# Main.net
KiCad netlist of a schematic drawn in Altium Designer
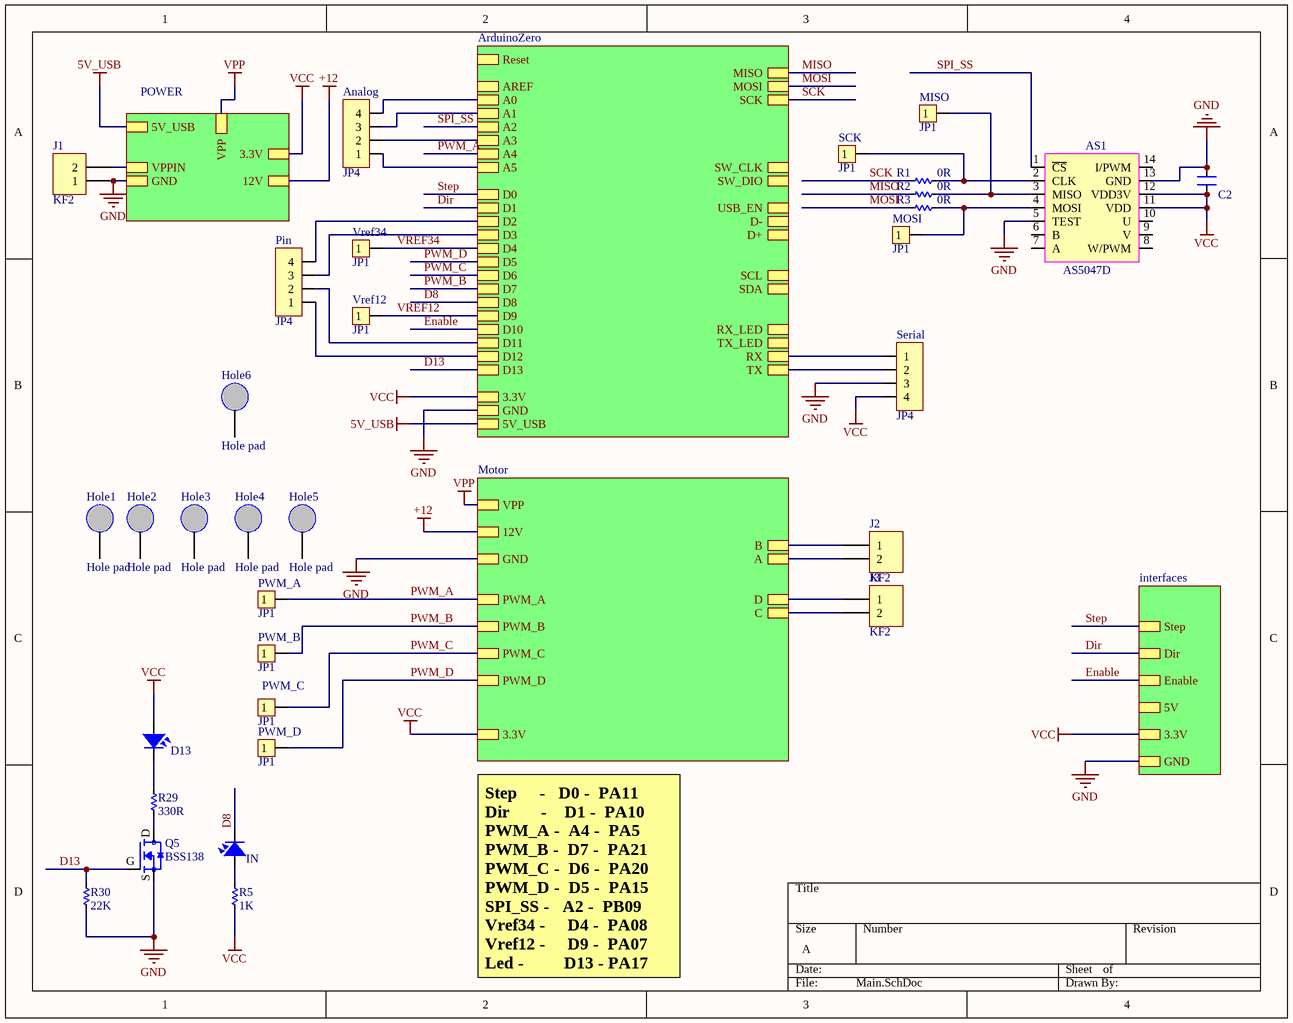
[diagram p0: Main.SchDoc]

(export (version "E")
  (design (tool "Eeschema 10.0.6"))
  (components
    (comp (ref "Analog")
      (value "JP4")
      (footprint "JP4-C1T")
      (description "WR-PHD 2.54 mm Angled Socket Header")
      (fields
        (field (name "MANUFACTURER") "Würth Elektronik eiSos GmbH")
        (field (name "PARTNO") "613004143121")
        (field (name "CREATED BY") "Karrer Zheng")
      )
      (libsource (lib "") (part "JP4_1"))
    )
    (comp (ref "AS1")
      (value "AS5047D")
      (footprint "AS5047D_Module")
      (fields (field (name "VOLTAGE") "0"))
      (libsource (lib "nhan") (part "AS5047D"))
    )
    (comp (ref "C2") (value "CN") (footprint "CN-SMD-0603_big") (libsource (lib "nhan") (part "CN")))
    (comp (ref "D13") (value "LED") (footprint "LED-0805-Blue") (libsource (lib "LIBRARY") (part "LED SMD")))
    (comp (ref "Hole1") (value "Hole pad") (footprint "HolePad") (libsource (lib "nhan") (part "Hole pad")))
    (comp (ref "Hole2") (value "Hole pad") (footprint "HolePad") (libsource (lib "nhan") (part "Hole pad")))
    (comp (ref "Hole3") (value "Hole pad") (footprint "HolePad") (libsource (lib "nhan") (part "Hole pad")))
    (comp (ref "Hole4") (value "Hole pad") (footprint "HolePad") (libsource (lib "nhan") (part "Hole pad")))
    (comp (ref "Hole5") (value "Hole pad") (footprint "HolePad") (libsource (lib "nhan") (part "Hole pad")))
    (comp (ref "Hole6") (value "Hole pad") (footprint "HolePad") (libsource (lib "nhan") (part "Hole pad")))
    (comp (ref "IN") (value "LED") (footprint "LED-0805-Blue") (libsource (lib "LIBRARY") (part "LED SMD")))
    (comp (ref "J1")
      (value "KF2")
      (footprint "KF2-5.08T")
      (fields
        (field (name "MANUFACTURER") "Würth Elektronik eiSos GmbH")
        (field (name "PARTNO") "691103110002")
        (field (name "CREATED BY") "Karrer Zheng")
      )
      (libsource (lib "") (part "KF2_1"))
    )
    (comp (ref "J2")
      (value "KF2")
      (footprint "KF2-5.08T")
      (fields
        (field (name "MANUFACTURER") "Würth Elektronik eiSos GmbH")
        (field (name "PARTNO") "691103110002")
        (field (name "CREATED BY") "Karrer Zheng")
      )
      (libsource (lib "BanLinhKien") (part "KF2"))
    )
    (comp (ref "J3")
      (value "KF2")
      (footprint "KF2-5.08T")
      (fields
        (field (name "MANUFACTURER") "Würth Elektronik eiSos GmbH")
        (field (name "PARTNO") "691103110002")
        (field (name "CREATED BY") "Karrer Zheng")
      )
      (libsource (lib "BanLinhKien") (part "KF2"))
    )
    (comp (ref "MISO")
      (value "JP1")
      (footprint "JP1-D1T")
      (description "WR-PHD 2.54 mm Angled Socket Header")
      (fields
        (field (name "MANUFACTURER") "Würth Elektronik eiSos GmbH")
        (field (name "PARTNO") "613002143121")
        (field (name "CREATED BY") "Karrer Zheng")
      )
      (libsource (lib "LIBRARY") (part "JP1"))
    )
    (comp (ref "MOSI")
      (value "JP1")
      (footprint "JP1-D1T")
      (description "WR-PHD 2.54 mm Angled Socket Header")
      (fields
        (field (name "MANUFACTURER") "Würth Elektronik eiSos GmbH")
        (field (name "PARTNO") "613002143121")
        (field (name "CREATED BY") "Karrer Zheng")
      )
      (libsource (lib "LIBRARY") (part "JP1"))
    )
    (comp (ref "Pin")
      (value "JP4")
      (footprint "JP4-C1T")
      (description "WR-PHD 2.54 mm Angled Socket Header")
      (fields
        (field (name "MANUFACTURER") "Würth Elektronik eiSos GmbH")
        (field (name "PARTNO") "613004143121")
        (field (name "CREATED BY") "Karrer Zheng")
      )
      (libsource (lib "") (part "JP4_1"))
    )
    (comp (ref "PWM_A")
      (value "JP1")
      (footprint "JP1-D1T")
      (description "WR-PHD 2.54 mm Angled Socket Header")
      (fields
        (field (name "MANUFACTURER") "Würth Elektronik eiSos GmbH")
        (field (name "PARTNO") "613002143121")
        (field (name "CREATED BY") "Karrer Zheng")
      )
      (libsource (lib "LIBRARY") (part "JP1"))
    )
    (comp (ref "PWM_B")
      (value "JP1")
      (footprint "JP1-D1T")
      (description "WR-PHD 2.54 mm Angled Socket Header")
      (fields
        (field (name "MANUFACTURER") "Würth Elektronik eiSos GmbH")
        (field (name "PARTNO") "613002143121")
        (field (name "CREATED BY") "Karrer Zheng")
      )
      (libsource (lib "LIBRARY") (part "JP1"))
    )
    (comp (ref "PWM_C")
      (value "JP1")
      (footprint "JP1-D1T")
      (description "WR-PHD 2.54 mm Angled Socket Header")
      (fields
        (field (name "MANUFACTURER") "Würth Elektronik eiSos GmbH")
        (field (name "PARTNO") "613002143121")
        (field (name "CREATED BY") "Karrer Zheng")
      )
      (libsource (lib "LIBRARY") (part "JP1"))
    )
    (comp (ref "PWM_D")
      (value "JP1")
      (footprint "JP1-D1T")
      (description "WR-PHD 2.54 mm Angled Socket Header")
      (fields
        (field (name "MANUFACTURER") "Würth Elektronik eiSos GmbH")
        (field (name "PARTNO") "613002143121")
        (field (name "CREATED BY") "Karrer Zheng")
      )
      (libsource (lib "LIBRARY") (part "JP1"))
    )
    (comp (ref "Q5")
      (value "BSS138")
      (footprint "SOT23-bss138")
      (description "N-Channel 50V 220mA _Ta_ 360mW _Ta_ Surface Mount Die")
      (fields (field (name "MF") "MICROSS/On Semiconductor"))
      (libsource (lib "nhan") (part "BSS138"))
    )
    (comp (ref "R1") (value "0R") (footprint "RES-SMD-0603_BIG") (libsource (lib "nhan") (part "R")))
    (comp (ref "R2") (value "0R") (footprint "RES-SMD-0603_BIG") (libsource (lib "nhan") (part "R")))
    (comp (ref "R3") (value "0R") (footprint "RES-SMD-0603_BIG") (libsource (lib "nhan") (part "R")))
    (comp (ref "R5") (value "1K") (footprint "RES-SMD-0603_BIG") (libsource (lib "nhan") (part "R")))
    (comp (ref "R29") (value "330R") (footprint "RES-SMD-0603_BIG") (libsource (lib "nhan") (part "R")))
    (comp (ref "R30") (value "22K") (footprint "RES-SMD-0603_BIG") (libsource (lib "nhan") (part "R")))
    (comp (ref "SCK")
      (value "JP1")
      (footprint "JP1-D1T")
      (description "WR-PHD 2.54 mm Angled Socket Header")
      (fields
        (field (name "MANUFACTURER") "Würth Elektronik eiSos GmbH")
        (field (name "PARTNO") "613002143121")
        (field (name "CREATED BY") "Karrer Zheng")
      )
      (libsource (lib "LIBRARY") (part "JP1"))
    )
    (comp (ref "Serial")
      (value "JP4")
      (footprint "JP4-C1T")
      (description "WR-PHD 2.54 mm Angled Socket Header")
      (fields
        (field (name "MANUFACTURER") "Würth Elektronik eiSos GmbH")
        (field (name "PARTNO") "613004143121")
        (field (name "CREATED BY") "Karrer Zheng")
      )
      (libsource (lib "LIBRARY") (part "JP4"))
    )
    (comp (ref "Vref12")
      (value "JP1")
      (footprint "JP1-D1T")
      (description "WR-PHD 2.54 mm Angled Socket Header")
      (fields
        (field (name "MANUFACTURER") "Würth Elektronik eiSos GmbH")
        (field (name "PARTNO") "613002143121")
        (field (name "CREATED BY") "Karrer Zheng")
      )
      (libsource (lib "LIBRARY") (part "JP1"))
    )
    (comp (ref "Vref34")
      (value "JP1")
      (footprint "JP1-D1T")
      (description "WR-PHD 2.54 mm Angled Socket Header")
      (fields
        (field (name "MANUFACTURER") "Würth Elektronik eiSos GmbH")
        (field (name "PARTNO") "613002143121")
        (field (name "CREATED BY") "Karrer Zheng")
      )
      (libsource (lib "LIBRARY") (part "JP1"))
    )
  )
  (nets
    (net (code "3") (name "/A") (class "Default")
      (node (ref "J2") (pin "2") (pinfunction "2_2") (pintype "passive"))
    )
    (net (code "4") (name "/A0") (class "Default")
      (node (ref "Analog") (pin "4") (pinfunction "4_4") (pintype "passive"))
    )
    (net (code "5") (name "/A1") (class "Default")
      (node (ref "Analog") (pin "3") (pinfunction "3_3") (pintype "passive"))
    )
    (net (code "6") (name "/A3") (class "Default")
      (node (ref "Analog") (pin "2") (pinfunction "2_2") (pintype "passive"))
    )
    (net (code "7") (name "/A5") (class "Default")
      (node (ref "Analog") (pin "1") (pinfunction "1_1") (pintype "passive"))
    )
    (net (code "9") (name "/B") (class "Default")
      (node (ref "J2") (pin "1") (pinfunction "1_1") (pintype "passive"))
    )
    (net (code "10") (name "/C") (class "Default")
      (node (ref "J3") (pin "2") (pinfunction "2_2") (pintype "passive"))
    )
    (net (code "11") (name "/D") (class "Default")
      (node (ref "J3") (pin "1") (pinfunction "1_1") (pintype "passive"))
    )
    (net (code "14") (name "/D2") (class "Default")
      (node (ref "Pin") (pin "4") (pinfunction "4_4") (pintype "passive"))
    )
    (net (code "15") (name "/D3") (class "Default")
      (node (ref "Pin") (pin "3") (pinfunction "3_3") (pintype "passive"))
    )
    (net (code "16") (name "/D8") (class "Default")
      (node (ref "IN") (pin "2") (pinfunction "2_2") (pintype "passive"))
    )
    (net (code "17") (name "/D11") (class "Default")
      (node (ref "Pin") (pin "2") (pinfunction "2_2") (pintype "passive"))
    )
    (net (code "18") (name "/D12") (class "Default")
      (node (ref "Pin") (pin "1") (pinfunction "1_1") (pintype "passive"))
    )
    (net (code "19") (name "/D13") (class "Default")
      (node (ref "Q5") (pin "G") (pinfunction "G_G") (pintype "passive"))
      (node (ref "R30") (pin "2") (pinfunction "2_2") (pintype "passive"))
    )
    (net (code "22") (name "/MISO") (class "Default")
      (node (ref "R2") (pin "2") (pinfunction "2_2") (pintype "passive"))
    )
    (net (code "23") (name "/MOSI") (class "Default")
      (node (ref "R3") (pin "2") (pinfunction "2_2") (pintype "passive"))
    )
    (net (code "24") (name "/PWM_A") (class "Default")
      (node (ref "PWM_A") (pin "1") (pinfunction "1_1") (pintype "passive"))
    )
    (net (code "25") (name "/PWM_B") (class "Default")
      (node (ref "PWM_B") (pin "1") (pinfunction "1_1") (pintype "passive"))
    )
    (net (code "26") (name "/PWM_C") (class "Default")
      (node (ref "PWM_C") (pin "1") (pinfunction "1_1") (pintype "passive"))
    )
    (net (code "27") (name "/PWM_D") (class "Default")
      (node (ref "PWM_D") (pin "1") (pinfunction "1_1") (pintype "passive"))
    )
    (net (code "28") (name "/RX") (class "Default")
      (node (ref "Serial") (pin "1") (pinfunction "1_1") (pintype "passive"))
    )
    (net (code "31") (name "/SCK") (class "Default")
      (node (ref "R1") (pin "2") (pinfunction "2_2") (pintype "passive"))
    )
    (net (code "34") (name "/SPI_SS") (class "Default")
      (node (ref "AS1") (pin "1") (pinfunction "CS_1") (pintype "passive"))
    )
    (net (code "38") (name "/TX") (class "Default")
      (node (ref "Serial") (pin "2") (pinfunction "2_2") (pintype "passive"))
    )
    (net (code "41") (name "/VPPIN") (class "Default")
      (node (ref "J1") (pin "2") (pinfunction "2_2") (pintype "passive"))
    )
    (net (code "42") (name "/VREF12") (class "Default")
      (node (ref "Vref12") (pin "1") (pinfunction "1_1") (pintype "passive"))
    )
    (net (code "43") (name "/VREF34") (class "Default")
      (node (ref "Vref34") (pin "1") (pinfunction "1_1") (pintype "passive"))
    )
    (net (code "45") (name "GND") (class "Default")
      (node (ref "AS1") (pin "13") (pinfunction "GND_13") (pintype "passive"))
      (node (ref "AS1") (pin "5") (pinfunction "TEST_5") (pintype "passive"))
      (node (ref "C2") (pin "2") (pinfunction "2_2") (pintype "passive"))
      (node (ref "J1") (pin "1") (pinfunction "1_1") (pintype "passive"))
      (node (ref "Q5") (pin "S") (pinfunction "S_S") (pintype "passive"))
      (node (ref "R30") (pin "1") (pinfunction "1_1") (pintype "passive"))
      (node (ref "Serial") (pin "3") (pinfunction "3_3") (pintype "passive"))
    )
    (net (code "46") (name "Net-(AS1-CLK)") (class "Default")
      (node (ref "AS1") (pin "2") (pinfunction "CLK_2") (pintype "passive"))
      (node (ref "R1") (pin "1") (pinfunction "1_1") (pintype "passive"))
      (node (ref "SCK") (pin "1") (pinfunction "1_1") (pintype "passive"))
    )
    (net (code "47") (name "Net-(AS1-MISO)") (class "Default")
      (node (ref "AS1") (pin "3") (pinfunction "MISO_3") (pintype "passive"))
      (node (ref "MISO") (pin "1") (pinfunction "1_1") (pintype "passive"))
      (node (ref "R2") (pin "1") (pinfunction "1_1") (pintype "passive"))
    )
    (net (code "48") (name "Net-(AS1-MOSI)") (class "Default")
      (node (ref "AS1") (pin "4") (pinfunction "MOSI_4") (pintype "passive"))
      (node (ref "MOSI") (pin "1") (pinfunction "1_1") (pintype "passive"))
      (node (ref "R3") (pin "1") (pinfunction "1_1") (pintype "passive"))
    )
    (net (code "49") (name "Net-(D13-Pad2)") (class "Default")
      (node (ref "D13") (pin "2") (pinfunction "2_2") (pintype "passive"))
      (node (ref "R29") (pin "1") (pinfunction "1_1") (pintype "passive"))
    )
    (net (code "50") (name "Net-(IN-Pad1)") (class "Default")
      (node (ref "IN") (pin "1") (pinfunction "1_1") (pintype "passive"))
      (node (ref "R5") (pin "1") (pinfunction "1_1") (pintype "passive"))
    )
    (net (code "51") (name "Net-(Q5-PadD)") (class "Default")
      (node (ref "Q5") (pin "D") (pinfunction "D_D") (pintype "passive"))
      (node (ref "R29") (pin "2") (pinfunction "2_2") (pintype "passive"))
    )
    (net (code "52") (name "VCC") (class "Default")
      (node (ref "AS1") (pin "11") (pinfunction "VDD_11") (pintype "passive"))
      (node (ref "AS1") (pin "12") (pinfunction "VDD3V_12") (pintype "passive"))
      (node (ref "C2") (pin "1") (pinfunction "1_1") (pintype "passive"))
      (node (ref "D13") (pin "1") (pinfunction "1_1") (pintype "passive"))
      (node (ref "R5") (pin "2") (pinfunction "2_2") (pintype "passive"))
      (node (ref "Serial") (pin "4") (pinfunction "4_4") (pintype "passive"))
    )
    (net (code "54") (name "unconnected-(AS1-A-Pad7)") (class "Default")
      (node (ref "AS1") (pin "7") (pinfunction "A_7") (pintype "passive"))
    )
    (net (code "55") (name "unconnected-(AS1-B-Pad6)") (class "Default")
      (node (ref "AS1") (pin "6") (pinfunction "B_6") (pintype "passive"))
    )
    (net (code "56") (name "unconnected-(AS1-I{slash}PWM-Pad14)") (class "Default")
      (node (ref "AS1") (pin "14") (pinfunction "I/PWM_14") (pintype "passive"))
    )
    (net (code "57") (name "unconnected-(AS1-U-Pad10)") (class "Default")
      (node (ref "AS1") (pin "10") (pinfunction "U_10") (pintype "passive"))
    )
    (net (code "58") (name "unconnected-(AS1-V-Pad9)") (class "Default")
      (node (ref "AS1") (pin "9") (pinfunction "V_9") (pintype "passive"))
    )
    (net (code "59") (name "unconnected-(AS1-W{slash}PWM-Pad8)") (class "Default")
      (node (ref "AS1") (pin "8") (pinfunction "W/PWM_8") (pintype "passive"))
    )
    (net (code "60") (name "unconnected-(Hole1-Pad1)") (class "Default")
      (node (ref "Hole1") (pin "1") (pinfunction "1_1") (pintype "passive"))
    )
    (net (code "61") (name "unconnected-(Hole2-Pad1)") (class "Default")
      (node (ref "Hole2") (pin "1") (pinfunction "1_1") (pintype "passive"))
    )
    (net (code "62") (name "unconnected-(Hole3-Pad1)") (class "Default")
      (node (ref "Hole3") (pin "1") (pinfunction "1_1") (pintype "passive"))
    )
    (net (code "63") (name "unconnected-(Hole4-Pad1)") (class "Default")
      (node (ref "Hole4") (pin "1") (pinfunction "1_1") (pintype "passive"))
    )
    (net (code "64") (name "unconnected-(Hole5-Pad1)") (class "Default")
      (node (ref "Hole5") (pin "1") (pinfunction "1_1") (pintype "passive"))
    )
    (net (code "65") (name "unconnected-(Hole6-Pad1)") (class "Default")
      (node (ref "Hole6") (pin "1") (pinfunction "1_1") (pintype "passive"))
    )
  )
)
